# stm32-lora.net
KiCad netlist of a schematic drawn in Altium Designer
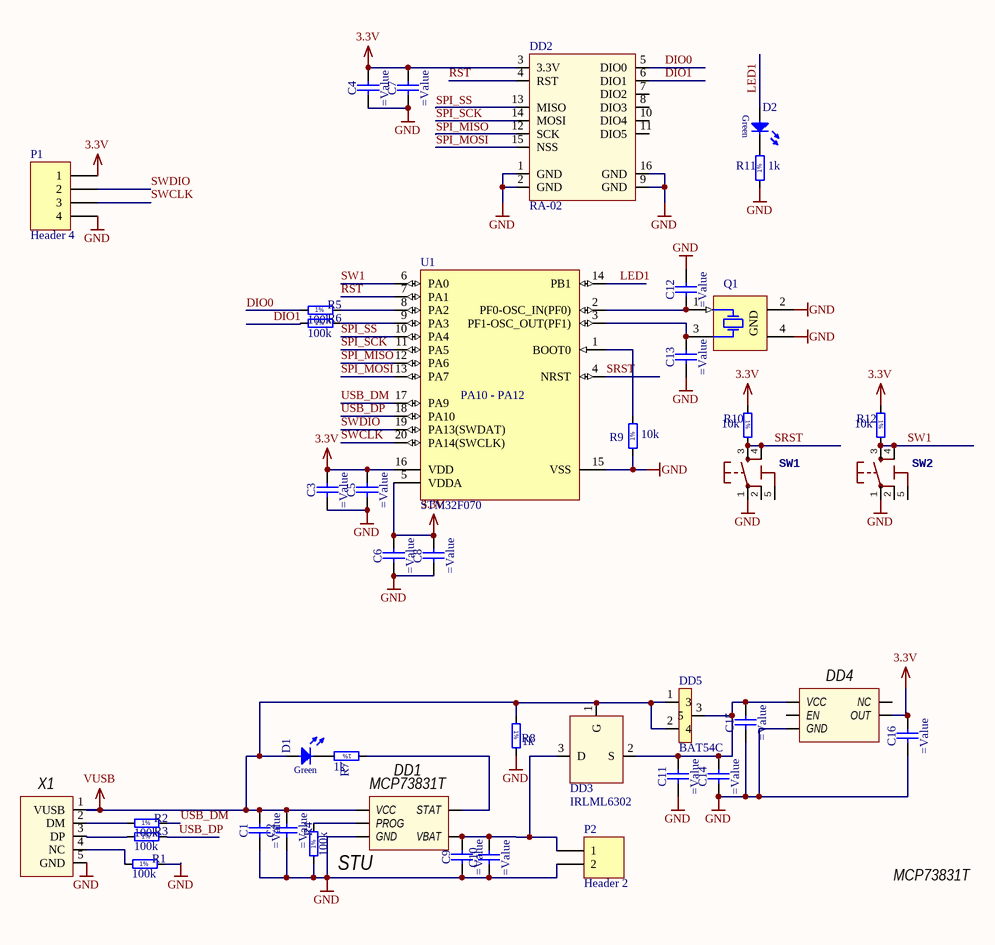
[diagram p0: stm32-lora.SchDoc]

(export (version "E")
  (design (tool "Eeschema 10.0.6"))
  (components
    (comp (ref "C1")
      (value "~")
      (footprint "CAPC2012X135N")
      (description "Non-polarised capacitor")
      (fields (field (name "PART NUMBER") "CC0805_1NF_50V_5%_X7R"))
      (libsource (lib "Capacitors") (part "Capacitor - non polarized"))
    )
    (comp (ref "C2")
      (value "~")
      (footprint "CAPC1608X85N")
      (description "Non-polarised capacitor")
      (fields (field (name "PART NUMBER") "CPPS0603_2.2NF_16V_5%_PANASONIC_ECHU(X)"))
      (libsource (lib "Capacitors") (part "Capacitor - non polarized"))
    )
    (comp (ref "C3")
      (value "~")
      (footprint "CAPC1608X85N")
      (description "Non-polarised capacitor")
      (fields (field (name "PART NUMBER") "CPPS0603_2.2NF_16V_5%_PANASONIC_ECHU(X)"))
      (libsource (lib "Capacitors") (part "Capacitor - non polarized"))
    )
    (comp (ref "C4")
      (value "~")
      (footprint "CAPC1608X85N")
      (description "Non-polarised capacitor")
      (fields (field (name "PART NUMBER") "CPPS0603_2.2NF_16V_5%_PANASONIC_ECHU(X)"))
      (libsource (lib "Capacitors") (part "Capacitor - non polarized"))
    )
    (comp (ref "C5")
      (value "~")
      (footprint "CAPC1608X85N")
      (description "Non-polarised capacitor")
      (fields (field (name "PART NUMBER") "CPPS0603_2.2NF_16V_5%_PANASONIC_ECHU(X)"))
      (libsource (lib "Capacitors") (part "Capacitor - non polarized"))
    )
    (comp (ref "C6")
      (value "~")
      (footprint "CAPC1608X85N")
      (description "Non-polarised capacitor")
      (fields (field (name "PART NUMBER") "CPPS0603_2.2NF_16V_5%_PANASONIC_ECHU(X)"))
      (libsource (lib "Capacitors") (part "Capacitor - non polarized"))
    )
    (comp (ref "C7")
      (value "~")
      (footprint "CAPC1608X85N")
      (description "Non-polarised capacitor")
      (fields (field (name "PART NUMBER") "CPPS0603_2.2NF_16V_5%_PANASONIC_ECHU(X)"))
      (libsource (lib "Capacitors") (part "Capacitor - non polarized"))
    )
    (comp (ref "C8")
      (value "~")
      (footprint "CAPC1608X85N")
      (description "Non-polarised capacitor")
      (fields (field (name "PART NUMBER") "CPPS0603_2.2NF_16V_5%_PANASONIC_ECHU(X)"))
      (libsource (lib "Capacitors") (part "Capacitor - non polarized"))
    )
    (comp (ref "C9")
      (value "~")
      (footprint "CAPC1608X85N")
      (description "Non-polarised capacitor")
      (fields (field (name "PART NUMBER") "CPPS0603_2.2NF_16V_5%_PANASONIC_ECHU(X)"))
      (libsource (lib "Capacitors") (part "Capacitor - non polarized"))
    )
    (comp (ref "C10")
      (value "~")
      (footprint "CAPC2012X135N")
      (description "Non-polarised capacitor")
      (fields (field (name "PART NUMBER") "CC0805_1NF_50V_5%_X7R"))
      (libsource (lib "Capacitors") (part "Capacitor - non polarized"))
    )
    (comp (ref "C11")
      (value "~")
      (footprint "CAPC2012X135N")
      (description "Non-polarised capacitor")
      (fields (field (name "PART NUMBER") "CC0805_1NF_50V_5%_X7R"))
      (libsource (lib "Capacitors") (part "Capacitor - non polarized"))
    )
    (comp (ref "C12")
      (value "~")
      (footprint "CAPC1608X85N")
      (description "Non-polarised capacitor")
      (fields (field (name "PART NUMBER") "CPPS0603_2.2NF_16V_5%_PANASONIC_ECHU(X)"))
      (libsource (lib "Capacitors") (part "Capacitor - non polarized"))
    )
    (comp (ref "C13")
      (value "~")
      (footprint "CAPC1608X85N")
      (description "Non-polarised capacitor")
      (fields (field (name "PART NUMBER") "CPPS0603_2.2NF_16V_5%_PANASONIC_ECHU(X)"))
      (libsource (lib "Capacitors") (part "Capacitor - non polarized"))
    )
    (comp (ref "C14")
      (value "~")
      (footprint "CAPC2012X135N")
      (description "Non-polarised capacitor")
      (fields (field (name "PART NUMBER") "CC0805_1NF_50V_5%_X7R"))
      (libsource (lib "Capacitors") (part "Capacitor - non polarized"))
    )
    (comp (ref "C15")
      (value "~")
      (footprint "CAPC1608X85N")
      (description "Non-polarised capacitor")
      (fields (field (name "PART NUMBER") "CPPS0603_2.2NF_16V_5%_PANASONIC_ECHU(X)"))
      (libsource (lib "Capacitors") (part "Capacitor - non polarized"))
    )
    (comp (ref "C16")
      (value "~")
      (footprint "CAPC1608X85N")
      (description "Non-polarised capacitor")
      (fields (field (name "PART NUMBER") "CPPS0603_2.2NF_16V_5%_PANASONIC_ECHU(X)"))
      (libsource (lib "Capacitors") (part "Capacitor - non polarized"))
    )
    (comp (ref "D1")
      (value "Green")
      (footprint "LED_OSRAM_LGL29K")
      (description "LED Green 1C 2A")
      (fields
        (field (name "PART NUMBER") "LED_OSRAM_LG L29K-G2J1-24-Z")
        (field (name "MANUFACTURER") "OSRAM")
        (field (name "AUTHOR") "CERN DEM JLC")
      )
      (libsource (lib "ICs And Semiconductors") (part "LED Green 1C 2A"))
    )
    (comp (ref "D2")
      (value "Green")
      (footprint "LED_OSRAM_LGL29K")
      (description "LED Green 1C 2A")
      (fields
        (field (name "PART NUMBER") "LED_OSRAM_LG L29K-G2J1-24-Z")
        (field (name "MANUFACTURER") "OSRAM")
        (field (name "AUTHOR") "CERN DEM JLC")
      )
      (libsource (lib "ICs And Semiconductors") (part "LED Green 1C 2A"))
    )
    (comp (ref "DD1")
      (value "MCP73831T")
      (footprint "SOT95P270X145-5N")
      (description "MCP73831T Li-ion/Li-po charger")
      (fields (field (name "PART NUMBER") "MCP73831/2  SOT-23-5"))
      (libsource (lib "Lib") (part "MCP73831T"))
    )
    (comp (ref "DD2") (value "RA-02") (footprint "ESP_12 - duplicate") (libsource (lib "Lib") (part "RA-02")))
    (comp (ref "DD3")
      (value "IRLML6302")
      (footprint "SOT95P245X110-3N")
      (libsource (lib "Lib") (part "IRLML6302"))
    )
    (comp (ref "DD4")
      (value "MCP73831T")
      (footprint "SOT95P270X145-5N")
      (description "MCP73831T Li-ion/Li-po charger")
      (fields (field (name "PART NUMBER") "MCP73831/2  SOT-23-5"))
      (libsource (lib "Lib") (part "MIC5504"))
    )
    (comp (ref "DD5") (value "BAT54C") (footprint "SOT95P245X110-3N") (libsource (lib "Lib") (part "BAT54C")))
    (comp (ref "P1")
      (value "Header 4")
      (footprint "HDR1X4")
      (description "Header, 4-Pin")
      (fields (field (name "PUBLISHER") "Altium Limited"))
      (libsource (lib "Miscellaneous Connectors") (part "Header 4"))
    )
    (comp (ref "P2")
      (value "Header 2")
      (footprint "HDR1X2")
      (description "Header, 2-Pin")
      (fields (field (name "PUBLISHER") "Altium Limited"))
      (libsource (lib "Miscellaneous Connectors") (part "Header 2"))
    )
    (comp (ref "Q1")
      (value "114.285MHZ")
      (footprint "XTAL_CONNOR_CS")
      (description "Crystal 4 pins 1=XTAL Control 2=GND3=XTAL 4=GND")
      (fields
        (field (name "PART NUMBER") "XTAL_114.285MHZ_CONNOR_CS-018")
        (field (name "MANUFACTURER") "CONNOR WINFIELD")
        (field (name "AUTHOR") "CERN DEM JLC")
      )
      (libsource (lib "ICs And Semiconductors") (part "Quartz Crystal 1X 2GND 3X 4GND"))
    )
    (comp (ref "R1")
      (value "100k")
      (footprint "RESC1608X55N")
      (description "Resistor - 1%")
      (fields (field (name "PART NUMBER") "R0603_2K7_1%_0.1W_100PPM"))
      (libsource (lib "Resistors") (part "Resistor - 1%"))
    )
    (comp (ref "R2")
      (value "100k")
      (footprint "RESC1608X55N")
      (description "Resistor - 1%")
      (fields (field (name "PART NUMBER") "R0603_2K7_1%_0.1W_100PPM"))
      (libsource (lib "Resistors") (part "Resistor - 1%"))
    )
    (comp (ref "R3")
      (value "100k")
      (footprint "RESC1608X55N")
      (description "Resistor - 1%")
      (fields (field (name "PART NUMBER") "R0603_2K7_1%_0.1W_100PPM"))
      (libsource (lib "Resistors") (part "Resistor - 1%"))
    )
    (comp (ref "R4")
      (value "100k")
      (footprint "RESC1608X55N")
      (description "Resistor - 1%")
      (fields (field (name "PART NUMBER") "R0603_2K7_1%_0.1W_100PPM"))
      (libsource (lib "Resistors") (part "Resistor - 1%"))
    )
    (comp (ref "R5")
      (value "100k")
      (footprint "RESC1608X55N")
      (description "Resistor - 1%")
      (fields (field (name "PART NUMBER") "R0603_2K7_1%_0.1W_100PPM"))
      (libsource (lib "Resistors") (part "Resistor - 1%"))
    )
    (comp (ref "R6")
      (value "100k")
      (footprint "RESC1608X55N")
      (description "Resistor - 1%")
      (fields (field (name "PART NUMBER") "R0603_2K7_1%_0.1W_100PPM"))
      (libsource (lib "Resistors") (part "Resistor - 1%"))
    )
    (comp (ref "R7")
      (value "1k")
      (footprint "RESC1608X55N")
      (description "Resistor - 1%")
      (fields
        (field (name "PART NUMBER") "R0603_2K7_1%_0.1W_100PPM")
        (field (name "POWER") "0.1W")
        (field (name "AUTHOR") "CERN DEM JLC")
      )
      (libsource (lib "Resistors") (part "Resistor - 1%"))
    )
    (comp (ref "R8")
      (value "1k")
      (footprint "RESC1608X55N")
      (description "Resistor - 1%")
      (fields
        (field (name "PART NUMBER") "R0603_2K7_1%_0.1W_100PPM")
        (field (name "POWER") "0.1W")
        (field (name "AUTHOR") "CERN DEM JLC")
      )
      (libsource (lib "Resistors") (part "Resistor - 1%"))
    )
    (comp (ref "R9")
      (value "10k")
      (footprint "RESC1608X55N")
      (description "Resistor - 1%")
      (fields
        (field (name "PART NUMBER") "R0603_2K7_1%_0.1W_100PPM")
        (field (name "POWER") "0.1W")
        (field (name "AUTHOR") "CERN DEM JLC")
      )
      (libsource (lib "Resistors") (part "Resistor - 1%"))
    )
    (comp (ref "R10")
      (value "10k")
      (footprint "RESC1608X55N")
      (description "Resistor - 1%")
      (fields
        (field (name "PART NUMBER") "R0603_2K7_1%_0.1W_100PPM")
        (field (name "POWER") "0.1W")
        (field (name "AUTHOR") "CERN DEM JLC")
      )
      (libsource (lib "Resistors") (part "Resistor - 1%"))
    )
    (comp (ref "R11")
      (value "1k")
      (footprint "RESC1608X55N")
      (description "Resistor - 1%")
      (fields
        (field (name "PART NUMBER") "R0603_2K7_1%_0.1W_100PPM")
        (field (name "POWER") "0.1W")
        (field (name "AUTHOR") "CERN DEM JLC")
      )
      (libsource (lib "Resistors") (part "Resistor - 1%"))
    )
    (comp (ref "R12")
      (value "10k")
      (footprint "RESC1608X55N")
      (description "Resistor - 1%")
      (fields
        (field (name "PART NUMBER") "R0603_2K7_1%_0.1W_100PPM")
        (field (name "POWER") "0.1W")
        (field (name "AUTHOR") "CERN DEM JLC")
      )
      (libsource (lib "Resistors") (part "Resistor - 1%"))
    )
    (comp (ref "SW1")
      (value "TS42 Dongnan Electronics Tact switch VDC 12V - 50mA")
      (footprint "TS42")
      (libsource (lib "Lib") (part "TS42"))
    )
    (comp (ref "SW2")
      (value "TS42 Dongnan Electronics Tact switch VDC 12V - 50mA")
      (footprint "TS42")
      (libsource (lib "Lib") (part "TS42"))
    )
    (comp (ref "U1")
      (value "STM32F070")
      (footprint "IC_all:SOP127P600-8N")
      (fields (field (name "PARTNUMBER") "STM32F050F6P6"))
      (libsource (lib "IC_all") (part "STM32F070F4P6"))
    )
    (comp (ref "X1")
      (value "uUSB")
      (footprint "USB-MICROB")
      (description "micro USB")
      (libsource (lib "Lib") (part "usb"))
    )
  )
  (nets
    (net (code "1") (name "/DIO0") (class "Default")
      (node (ref "DD2") (pin "5") (pinfunction "DIO0_5") (pintype "passive"))
      (node (ref "R5") (pin "1") (pinfunction "1_1") (pintype "passive"))
    )
    (net (code "2") (name "/DIO1") (class "Default")
      (node (ref "DD2") (pin "6") (pinfunction "DIO1_6") (pintype "passive"))
      (node (ref "R6") (pin "1") (pinfunction "1_1") (pintype "passive"))
    )
    (net (code "3") (name "/LED1") (class "Default")
      (node (ref "D2") (pin "2") (pinfunction "A_2") (pintype "passive"))
      (node (ref "U1") (pin "14") (pinfunction "PB1_14") (pintype "bidirectional"))
    )
    (net (code "4") (name "/RST") (class "Default")
      (node (ref "DD2") (pin "4") (pinfunction "RST_4") (pintype "passive"))
      (node (ref "U1") (pin "7") (pinfunction "PA1_7") (pintype "bidirectional"))
    )
    (net (code "5") (name "/SPI_MISO") (class "Default")
      (node (ref "DD2") (pin "12") (pinfunction "SCK_12") (pintype "passive"))
      (node (ref "U1") (pin "12") (pinfunction "PA6_12") (pintype "bidirectional"))
    )
    (net (code "6") (name "/SPI_MOSI") (class "Default")
      (node (ref "DD2") (pin "15") (pinfunction "NSS_15") (pintype "passive"))
      (node (ref "U1") (pin "13") (pinfunction "PA7_13") (pintype "bidirectional"))
    )
    (net (code "7") (name "/SPI_SCK") (class "Default")
      (node (ref "DD2") (pin "14") (pinfunction "MOSI_14") (pintype "passive"))
      (node (ref "U1") (pin "11") (pinfunction "PA5_11") (pintype "bidirectional"))
    )
    (net (code "8") (name "/SPI_SS") (class "Default")
      (node (ref "DD2") (pin "13") (pinfunction "MISO_13") (pintype "passive"))
      (node (ref "U1") (pin "10") (pinfunction "PA4_10") (pintype "bidirectional"))
    )
    (net (code "9") (name "/SRST") (class "Default")
      (node (ref "R10") (pin "2") (pinfunction "2_2") (pintype "passive"))
      (node (ref "SW1") (pin "3") (pinfunction "3_3") (pintype "passive"))
      (node (ref "SW1") (pin "4") (pinfunction "4_4") (pintype "passive"))
      (node (ref "U1") (pin "4") (pinfunction "NRST_4") (pintype "bidirectional"))
    )
    (net (code "10") (name "/SW1") (class "Default")
      (node (ref "R12") (pin "2") (pinfunction "2_2") (pintype "passive"))
      (node (ref "SW2") (pin "3") (pinfunction "3_3") (pintype "passive"))
      (node (ref "SW2") (pin "4") (pinfunction "4_4") (pintype "passive"))
      (node (ref "U1") (pin "6") (pinfunction "PA0_6") (pintype "bidirectional"))
    )
    (net (code "11") (name "/SWCLK") (class "Default")
      (node (ref "P1") (pin "3") (pinfunction "3_3") (pintype "passive"))
      (node (ref "U1") (pin "20") (pinfunction "PA14(SWCLK)_20") (pintype "bidirectional"))
    )
    (net (code "12") (name "/SWDIO") (class "Default")
      (node (ref "P1") (pin "2") (pinfunction "2_2") (pintype "passive"))
      (node (ref "U1") (pin "19") (pinfunction "PA13(SWDAT)_19") (pintype "bidirectional"))
    )
    (net (code "13") (name "/USB_DM") (class "Default")
      (node (ref "R2") (pin "2") (pinfunction "2_2") (pintype "passive"))
      (node (ref "U1") (pin "17") (pinfunction "PA9_17") (pintype "bidirectional"))
    )
    (net (code "14") (name "/USB_DP") (class "Default")
      (node (ref "R3") (pin "2") (pinfunction "2_2") (pintype "passive"))
      (node (ref "U1") (pin "18") (pinfunction "PA10_18") (pintype "bidirectional"))
    )
    (net (code "15") (name "3.3V") (class "Default")
      (node (ref "C16") (pin "2") (pinfunction "2_2") (pintype "passive"))
      (node (ref "C3") (pin "2") (pinfunction "2_2") (pintype "passive"))
      (node (ref "C4") (pin "2") (pinfunction "2_2") (pintype "passive"))
      (node (ref "C5") (pin "2") (pinfunction "2_2") (pintype "passive"))
      (node (ref "C6") (pin "2") (pinfunction "2_2") (pintype "passive"))
      (node (ref "C7") (pin "2") (pinfunction "2_2") (pintype "passive"))
      (node (ref "C8") (pin "2") (pinfunction "2_2") (pintype "passive"))
      (node (ref "DD2") (pin "3") (pinfunction "3.3V_3") (pintype "passive"))
      (node (ref "DD4") (pin "5") (pinfunction "OUT_5") (pintype "passive"))
      (node (ref "P1") (pin "1") (pinfunction "1_1") (pintype "passive"))
      (node (ref "R10") (pin "1") (pinfunction "1_1") (pintype "passive"))
      (node (ref "R12") (pin "1") (pinfunction "1_1") (pintype "passive"))
      (node (ref "U1") (pin "16") (pinfunction "VDD_16") (pintype "power_in"))
      (node (ref "U1") (pin "5") (pinfunction "VDDA_5") (pintype "power_in"))
    )
    (net (code "16") (name "GND") (class "Default")
      (node (ref "C1") (pin "1") (pinfunction "1_1") (pintype "passive"))
      (node (ref "C10") (pin "1") (pinfunction "1_1") (pintype "passive"))
      (node (ref "C11") (pin "1") (pinfunction "1_1") (pintype "passive"))
      (node (ref "C12") (pin "2") (pinfunction "2_2") (pintype "passive"))
      (node (ref "C13") (pin "1") (pinfunction "1_1") (pintype "passive"))
      (node (ref "C14") (pin "1") (pinfunction "1_1") (pintype "passive"))
      (node (ref "C15") (pin "1") (pinfunction "1_1") (pintype "passive"))
      (node (ref "C16") (pin "1") (pinfunction "1_1") (pintype "passive"))
      (node (ref "C2") (pin "1") (pinfunction "1_1") (pintype "passive"))
      (node (ref "C3") (pin "1") (pinfunction "1_1") (pintype "passive"))
      (node (ref "C4") (pin "1") (pinfunction "1_1") (pintype "passive"))
      (node (ref "C5") (pin "1") (pinfunction "1_1") (pintype "passive"))
      (node (ref "C6") (pin "1") (pinfunction "1_1") (pintype "passive"))
      (node (ref "C7") (pin "1") (pinfunction "1_1") (pintype "passive"))
      (node (ref "C8") (pin "1") (pinfunction "1_1") (pintype "passive"))
      (node (ref "C9") (pin "1") (pinfunction "1_1") (pintype "passive"))
      (node (ref "DD1") (pin "2") (pinfunction "GND_2") (pintype "passive"))
      (node (ref "DD2") (pin "1") (pinfunction "GND_1") (pintype "passive"))
      (node (ref "DD2") (pin "16") (pinfunction "GND_16") (pintype "passive"))
      (node (ref "DD2") (pin "2") (pinfunction "GND_2") (pintype "passive"))
      (node (ref "DD2") (pin "9") (pinfunction "GND_9") (pintype "passive"))
      (node (ref "DD4") (pin "2") (pinfunction "GND_2") (pintype "passive"))
      (node (ref "P1") (pin "4") (pinfunction "4_4") (pintype "passive"))
      (node (ref "P2") (pin "2") (pinfunction "2_2") (pintype "passive"))
      (node (ref "Q1") (pin "2") (pinfunction "GND_2") (pintype "power_in"))
      (node (ref "Q1") (pin "4") (pinfunction "GND_4") (pintype "power_in"))
      (node (ref "R1") (pin "2") (pinfunction "2_2") (pintype "passive"))
      (node (ref "R11") (pin "1") (pinfunction "1_1") (pintype "passive"))
      (node (ref "R4") (pin "1") (pinfunction "1_1") (pintype "passive"))
      (node (ref "R8") (pin "2") (pinfunction "2_2") (pintype "passive"))
      (node (ref "R9") (pin "1") (pinfunction "1_1") (pintype "passive"))
      (node (ref "SW1") (pin "1") (pinfunction "1_1") (pintype "passive"))
      (node (ref "SW2") (pin "1") (pinfunction "1_1") (pintype "passive"))
      (node (ref "U1") (pin "15") (pinfunction "VSS_15") (pintype "power_in"))
      (node (ref "X1") (pin "5") (pinfunction "GND_5") (pintype "passive"))
    )
    (net (code "17") (name "Net-(D1-C)") (class "Default")
      (node (ref "D1") (pin "1") (pinfunction "C_1") (pintype "passive"))
      (node (ref "R7") (pin "2") (pinfunction "2_2") (pintype "passive"))
    )
    (net (code "18") (name "Net-(D2-C)") (class "Default")
      (node (ref "D2") (pin "1") (pinfunction "C_1") (pintype "passive"))
      (node (ref "R11") (pin "2") (pinfunction "2_2") (pintype "passive"))
    )
    (net (code "19") (name "Net-(DD1-PROG)") (class "Default")
      (node (ref "DD1") (pin "5") (pinfunction "PROG_5") (pintype "passive"))
      (node (ref "R4") (pin "2") (pinfunction "2_2") (pintype "passive"))
    )
    (net (code "20") (name "Net-(DD1-STAT)") (class "Default")
      (node (ref "DD1") (pin "1") (pinfunction "STAT_1") (pintype "passive"))
      (node (ref "R7") (pin "1") (pinfunction "1_1") (pintype "passive"))
    )
    (net (code "21") (name "Net-(DD1-VBAT)") (class "Default")
      (node (ref "C10") (pin "2") (pinfunction "2_2") (pintype "passive"))
      (node (ref "C9") (pin "2") (pinfunction "2_2") (pintype "passive"))
      (node (ref "DD1") (pin "3") (pinfunction "VBAT_3") (pintype "passive"))
      (node (ref "DD3") (pin "3") (pinfunction "D_3") (pintype "passive"))
      (node (ref "P2") (pin "1") (pinfunction "1_1") (pintype "passive"))
    )
    (net (code "22") (name "Net-(DD3-S)") (class "Default")
      (node (ref "C11") (pin "2") (pinfunction "2_2") (pintype "passive"))
      (node (ref "C14") (pin "2") (pinfunction "2_2") (pintype "passive"))
      (node (ref "C15") (pin "2") (pinfunction "2_2") (pintype "passive"))
      (node (ref "DD3") (pin "2") (pinfunction "S_2") (pintype "passive"))
      (node (ref "DD4") (pin "4") (pinfunction "VCC_4") (pintype "passive"))
      (node (ref "DD5") (pin "3") (pinfunction "5_3") (pintype "passive"))
    )
    (net (code "23") (name "Net-(U1-BOOT0)") (class "Default")
      (node (ref "R9") (pin "2") (pinfunction "2_2") (pintype "passive"))
      (node (ref "U1") (pin "1") (pinfunction "BOOT0_1") (pintype "input"))
    )
    (net (code "24") (name "Net-(U1-PA2)") (class "Default")
      (node (ref "R5") (pin "2") (pinfunction "2_2") (pintype "passive"))
      (node (ref "U1") (pin "8") (pinfunction "PA2_8") (pintype "bidirectional"))
    )
    (net (code "25") (name "Net-(U1-PA3)") (class "Default")
      (node (ref "R6") (pin "2") (pinfunction "2_2") (pintype "passive"))
      (node (ref "U1") (pin "9") (pinfunction "PA3_9") (pintype "bidirectional"))
    )
    (net (code "26") (name "Net-(U1-PF0-OSC_IN(PF0))") (class "Default")
      (node (ref "C12") (pin "1") (pinfunction "1_1") (pintype "passive"))
      (node (ref "Q1") (pin "1") (pinfunction "X_1") (pintype "input"))
      (node (ref "U1") (pin "2") (pinfunction "PF0-OSC_IN(PF0)_2") (pintype "bidirectional"))
    )
    (net (code "27") (name "Net-(U1-PF1-OSC_OUT(PF1))") (class "Default")
      (node (ref "C13") (pin "2") (pinfunction "2_2") (pintype "passive"))
      (node (ref "Q1") (pin "3") (pinfunction "X_3") (pintype "power_in"))
      (node (ref "U1") (pin "3") (pinfunction "PF1-OSC_OUT(PF1)_3") (pintype "bidirectional"))
    )
    (net (code "28") (name "Net-(X1-DM)") (class "Default")
      (node (ref "R2") (pin "1") (pinfunction "1_1") (pintype "passive"))
      (node (ref "X1") (pin "2") (pinfunction "DM_2") (pintype "passive"))
    )
    (net (code "29") (name "Net-(X1-DP)") (class "Default")
      (node (ref "R3") (pin "1") (pinfunction "1_1") (pintype "passive"))
      (node (ref "X1") (pin "3") (pinfunction "DP_3") (pintype "passive"))
    )
    (net (code "30") (name "Net-(X1-NC)") (class "Default")
      (node (ref "R1") (pin "1") (pinfunction "1_1") (pintype "passive"))
      (node (ref "X1") (pin "4") (pinfunction "NC_4") (pintype "passive"))
    )
    (net (code "31") (name "VUSB") (class "Default")
      (node (ref "C1") (pin "2") (pinfunction "2_2") (pintype "passive"))
      (node (ref "C2") (pin "2") (pinfunction "2_2") (pintype "passive"))
      (node (ref "D1") (pin "2") (pinfunction "A_2") (pintype "passive"))
      (node (ref "DD1") (pin "4") (pinfunction "VCC_4") (pintype "passive"))
      (node (ref "DD3") (pin "1") (pinfunction "G_1") (pintype "passive"))
      (node (ref "DD5") (pin "1") (pinfunction "3_1") (pintype "passive"))
      (node (ref "DD5") (pin "2") (pinfunction "4_2") (pintype "passive"))
      (node (ref "R8") (pin "1") (pinfunction "1_1") (pintype "passive"))
      (node (ref "X1") (pin "1") (pinfunction "VUSB_1") (pintype "passive"))
    )
    (net (code "32") (name "unconnected-(DD2-DIO2-Pad7)") (class "Default")
      (node (ref "DD2") (pin "7") (pinfunction "DIO2_7") (pintype "passive"))
    )
    (net (code "33") (name "unconnected-(DD2-DIO3-Pad8)") (class "Default")
      (node (ref "DD2") (pin "8") (pinfunction "DIO3_8") (pintype "passive"))
    )
    (net (code "34") (name "unconnected-(DD2-DIO4-Pad10)") (class "Default")
      (node (ref "DD2") (pin "10") (pinfunction "DIO4_10") (pintype "passive"))
    )
    (net (code "35") (name "unconnected-(DD2-DIO5-Pad11)") (class "Default")
      (node (ref "DD2") (pin "11") (pinfunction "DIO5_11") (pintype "passive"))
    )
    (net (code "36") (name "unconnected-(DD4-EN-Pad3)") (class "Default")
      (node (ref "DD4") (pin "3") (pinfunction "EN_3") (pintype "passive"))
    )
    (net (code "37") (name "unconnected-(DD4-NC-Pad4)") (class "Default")
      (node (ref "DD4") (pin "4") (pinfunction "NC_4") (pintype "passive"))
    )
    (net (code "38") (name "unconnected-(SW1-5-GND-Pad5)") (class "Default")
      (node (ref "SW1") (pin "5") (pinfunction "5-GND_5") (pintype "power_in"))
    )
    (net (code "39") (name "unconnected-(SW1-Pad2)") (class "Default")
      (node (ref "SW1") (pin "2") (pinfunction "2_2") (pintype "passive"))
    )
    (net (code "40") (name "unconnected-(SW2-5-GND-Pad5)") (class "Default")
      (node (ref "SW2") (pin "5") (pinfunction "5-GND_5") (pintype "power_in"))
    )
    (net (code "41") (name "unconnected-(SW2-Pad2)") (class "Default")
      (node (ref "SW2") (pin "2") (pinfunction "2_2") (pintype "passive"))
    )
  )
)
